# ControllerV2_1_2.net
KiCad netlist of a schematic drawn in Altium Designer
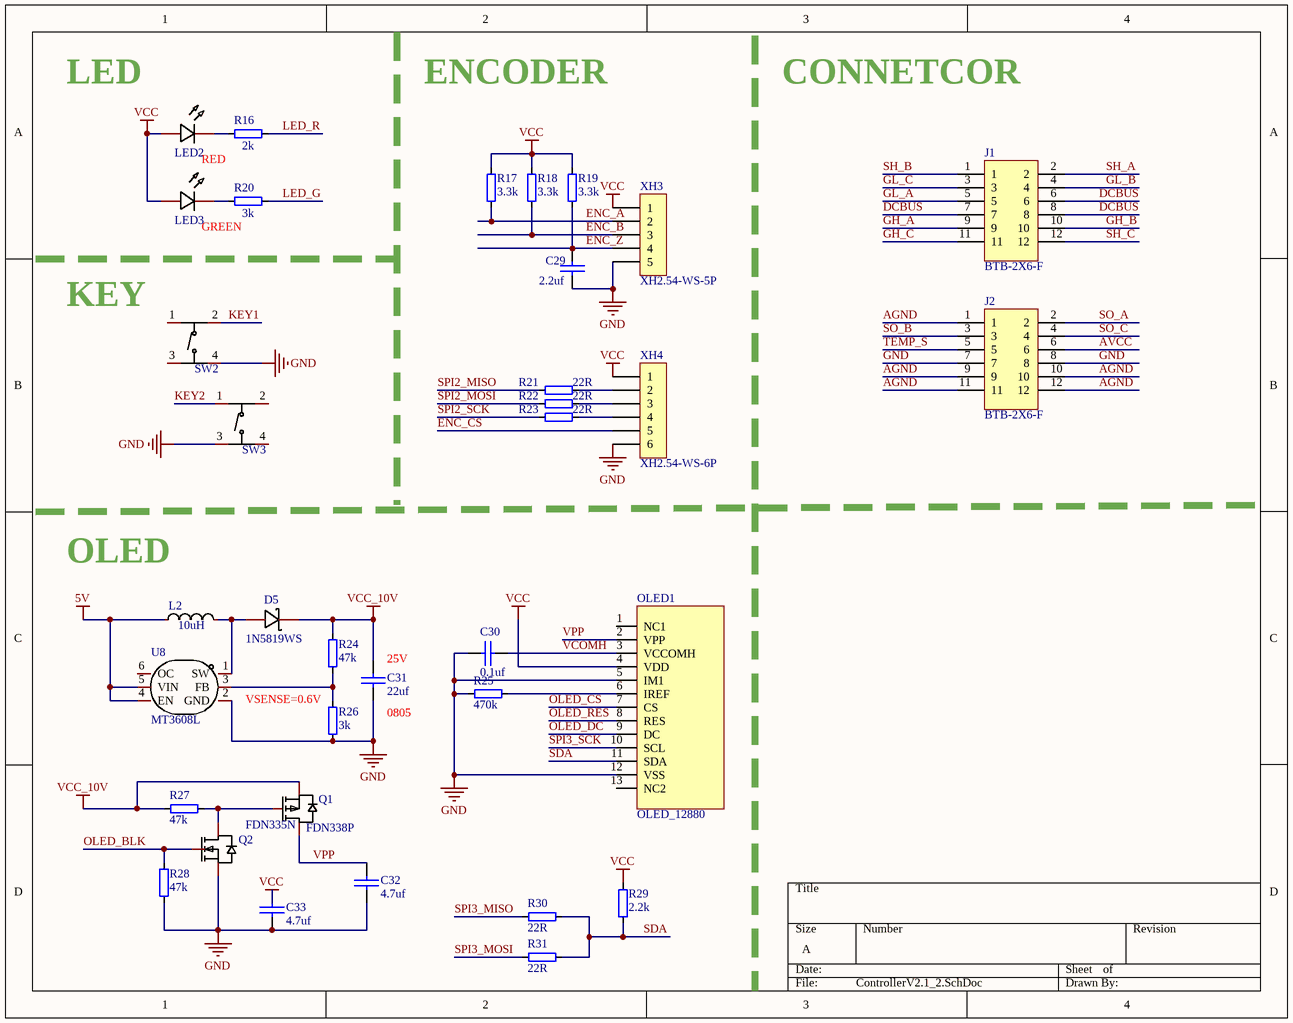
[diagram p0: ControllerV2.1_2.SchDoc]

(export (version "E")
  (design (tool "Eeschema 10.0.6"))
  (components
    (comp (ref "C29")
      (value "2.2uf")
      (footprint "0603C")
      (description "贴片电容")
      (libsource (lib "Controller") (part "CAP"))
    )
    (comp (ref "C30")
      (value "0.1uf")
      (footprint "0603C")
      (description "贴片电容")
      (libsource (lib "Controller") (part "CAP"))
    )
    (comp (ref "C31")
      (value "22uf")
      (footprint "0805C")
      (description "贴片电容")
      (libsource (lib "Controller") (part "CAP"))
    )
    (comp (ref "C32")
      (value "4.7uf")
      (footprint "0603C")
      (description "贴片电容")
      (libsource (lib "Controller") (part "CAP"))
    )
    (comp (ref "C33")
      (value "4.7uf")
      (footprint "0603C")
      (description "贴片电容")
      (libsource (lib "Controller") (part "CAP"))
    )
    (comp (ref "D5")
      (value "1N5819WS")
      (footprint "SOD-323")
      (description "肖特基二极管")
      (fields (field (name "MANUFACTURER") "Hottech(合科泰)"))
      (libsource (lib "Controller") (part "1N5819WS"))
    )
    (comp (ref "J1")
      (value "BTB-2X6-F")
      (footprint "BTB-F-0.8mm-2x6P")
      (description "0.8间距2x6P母座")
      (libsource (lib "Controller") (part "BTB-2X6-F"))
    )
    (comp (ref "J2")
      (value "BTB-2X6-F")
      (footprint "BTB-F-0.8mm-2x6P")
      (description "0.8间距2x6P母座")
      (libsource (lib "Controller") (part "BTB-2X6-F"))
    )
    (comp (ref "L2")
      (value "10uH")
      (footprint "IND-SMD_L3.0-W3.0_SWPA3010S")
      (description "电感值:10uH;精度:±20%;额定电流:920mA;")
      (fields (field (name "MANUFACTURER") "SXN(顺翔诺)") (field (name "MANUFACTURER PART") "SMDRI74-220M"))
      (libsource (lib "Controller") (part "SWPA3015S100MT"))
    )
    (comp (ref "LED2")
      (value "LED_0603-B")
      (footprint "LED_0603")
      (libsource (lib "Controller") (part "LED"))
    )
    (comp (ref "LED3")
      (value "LED_0603-B")
      (footprint "LED_0603")
      (libsource (lib "Controller") (part "LED"))
    )
    (comp (ref "OLED1")
      (value "OLED_12880")
      (footprint "OLED_12880")
      (description "OLED_128*80")
      (libsource (lib "Controller") (part "OLED_12880"))
    )
    (comp (ref "Q1")
      (value "FDN338P")
      (footprint "SOT-23-3")
      (description "P沟道 耐压:20V 电流:2A")
      (fields (field (name "MANUFACTURER") "TECH PUBLIC(台舟)"))
      (libsource (lib "Controller") (part "FDN338P"))
    )
    (comp (ref "Q2")
      (value "FDN335N")
      (footprint "SOT-23-3")
      (description "N沟道 耐压:20V 电流:1.7A")
      (fields (field (name "MANUFACTURER") "TECH PUBLIC(台舟)"))
      (libsource (lib "Controller") (part "FDN335N"))
    )
    (comp (ref "R16")
      (value "2k")
      (footprint "0603R")
      (description "贴片电阻")
      (libsource (lib "Controller") (part "RES"))
    )
    (comp (ref "R17")
      (value "3.3k")
      (footprint "0603R")
      (description "贴片电阻")
      (libsource (lib "Controller") (part "RES"))
    )
    (comp (ref "R18")
      (value "3.3k")
      (footprint "0603R")
      (description "贴片电阻")
      (libsource (lib "Controller") (part "RES"))
    )
    (comp (ref "R19")
      (value "3.3k")
      (footprint "0603R")
      (description "贴片电阻")
      (libsource (lib "Controller") (part "RES"))
    )
    (comp (ref "R20")
      (value "3k")
      (footprint "0603R")
      (description "贴片电阻")
      (libsource (lib "Controller") (part "RES"))
    )
    (comp (ref "R21")
      (value "22R")
      (footprint "0603R")
      (description "贴片电阻")
      (libsource (lib "Controller") (part "RES"))
    )
    (comp (ref "R22")
      (value "22R")
      (footprint "0603R")
      (description "贴片电阻")
      (libsource (lib "Controller") (part "RES"))
    )
    (comp (ref "R23")
      (value "22R")
      (footprint "0603R")
      (description "贴片电阻")
      (libsource (lib "Controller") (part "RES"))
    )
    (comp (ref "R24")
      (value "47k")
      (footprint "0603R")
      (description "贴片电阻")
      (libsource (lib "Controller") (part "RES"))
    )
    (comp (ref "R25")
      (value "470k")
      (footprint "0603R")
      (description "贴片电阻")
      (libsource (lib "Controller") (part "RES"))
    )
    (comp (ref "R26")
      (value "3k")
      (footprint "0603R")
      (description "贴片电阻")
      (libsource (lib "Controller") (part "RES"))
    )
    (comp (ref "R27")
      (value "47k")
      (footprint "0603R")
      (description "贴片电阻")
      (libsource (lib "Controller") (part "RES"))
    )
    (comp (ref "R28")
      (value "47k")
      (footprint "0603R")
      (description "贴片电阻")
      (libsource (lib "Controller") (part "RES"))
    )
    (comp (ref "R29")
      (value "2.2k")
      (footprint "0603R")
      (description "贴片电阻")
      (libsource (lib "Controller") (part "RES"))
    )
    (comp (ref "R30")
      (value "22R")
      (footprint "0603R")
      (description "贴片电阻")
      (libsource (lib "Controller") (part "RES"))
    )
    (comp (ref "R31")
      (value "22R")
      (footprint "0603R")
      (description "贴片电阻")
      (libsource (lib "Controller") (part "RES"))
    )
    (comp (ref "SW2")
      (value "TS-1187A-B-A-B")
      (footprint "TSW SMD-4*4*1.5")
      (description "轻触开关")
      (fields (field (name "MANUFACTURER") "XKB Connectivity(中国星坤)"))
      (libsource (lib "Controller") (part "TS-1187A-B-A-B"))
    )
    (comp (ref "SW3")
      (value "TS-1187A-B-A-B")
      (footprint "TSW SMD-4*4*1.5")
      (description "轻触开关")
      (fields (field (name "MANUFACTURER") "XKB Connectivity(中国星坤)"))
      (libsource (lib "Controller") (part "TS-1187A-B-A-B"))
    )
    (comp (ref "U8")
      (value "MT3608L")
      (footprint "SOT-23-6")
      (fields (field (name "MANUFACTURER") "西安航天民芯"))
      (libsource (lib "Controller") (part "MT3608L"))
    )
    (comp (ref "XH3")
      (value "XH2.54-WS-5P")
      (footprint "XH2.54-WS-5P")
      (libsource (lib "Controller") (part "XH2.54-WS-5P"))
    )
    (comp (ref "XH4")
      (value "XH2.54-WS-6P")
      (footprint "XH2.54-WS-6P")
      (libsource (lib "Controller") (part "XH2.54-WS-6P"))
    )
  )
  (nets
    (net (code "1") (name "/AGND") (class "Default")
      (node (ref "J2") (pin "1") (pinfunction "1_1") (pintype "passive"))
      (node (ref "J2") (pin "10") (pinfunction "10_10") (pintype "passive"))
      (node (ref "J2") (pin "11") (pinfunction "11_11") (pintype "passive"))
      (node (ref "J2") (pin "12") (pinfunction "12_12") (pintype "passive"))
      (node (ref "J2") (pin "9") (pinfunction "9_9") (pintype "passive"))
    )
    (net (code "2") (name "/AVCC") (class "Default")
      (node (ref "J2") (pin "6") (pinfunction "6_6") (pintype "passive"))
    )
    (net (code "3") (name "/DCBUS") (class "Default")
      (node (ref "J1") (pin "6") (pinfunction "6_6") (pintype "passive"))
      (node (ref "J1") (pin "7") (pinfunction "7_7") (pintype "passive"))
      (node (ref "J1") (pin "8") (pinfunction "8_8") (pintype "passive"))
    )
    (net (code "4") (name "/ENC_A") (class "Default")
      (node (ref "R17") (pin "1") (pinfunction "1_1") (pintype "passive"))
      (node (ref "XH3") (pin "2") (pinfunction "2_2") (pintype "passive"))
    )
    (net (code "5") (name "/ENC_B") (class "Default")
      (node (ref "R18") (pin "1") (pinfunction "1_1") (pintype "passive"))
      (node (ref "XH3") (pin "3") (pinfunction "3_3") (pintype "passive"))
    )
    (net (code "6") (name "/ENC_CS") (class "Default")
      (node (ref "XH4") (pin "5") (pinfunction "5_5") (pintype "passive"))
    )
    (net (code "7") (name "/ENC_Z") (class "Default")
      (node (ref "C29") (pin "1") (pinfunction "1_1") (pintype "passive"))
      (node (ref "R19") (pin "1") (pinfunction "1_1") (pintype "passive"))
      (node (ref "XH3") (pin "4") (pinfunction "4_4") (pintype "passive"))
    )
    (net (code "8") (name "/GH_A") (class "Default")
      (node (ref "J1") (pin "9") (pinfunction "9_9") (pintype "passive"))
    )
    (net (code "9") (name "/GH_B") (class "Default")
      (node (ref "J1") (pin "10") (pinfunction "10_10") (pintype "passive"))
    )
    (net (code "10") (name "/GH_C") (class "Default")
      (node (ref "J1") (pin "11") (pinfunction "11_11") (pintype "passive"))
    )
    (net (code "11") (name "/GL_A") (class "Default")
      (node (ref "J1") (pin "5") (pinfunction "5_5") (pintype "passive"))
    )
    (net (code "12") (name "/GL_B") (class "Default")
      (node (ref "J1") (pin "4") (pinfunction "4_4") (pintype "passive"))
    )
    (net (code "13") (name "/GL_C") (class "Default")
      (node (ref "J1") (pin "3") (pinfunction "3_3") (pintype "passive"))
    )
    (net (code "14") (name "/KEY1") (class "Default")
      (node (ref "SW2") (pin "2") (pinfunction "B_2") (pintype "passive"))
    )
    (net (code "15") (name "/KEY2") (class "Default")
      (node (ref "SW3") (pin "1") (pinfunction "A_1") (pintype "passive"))
    )
    (net (code "16") (name "/LED_G") (class "Default")
      (node (ref "R20") (pin "2") (pinfunction "2_2") (pintype "passive"))
    )
    (net (code "17") (name "/LED_R") (class "Default")
      (node (ref "R16") (pin "2") (pinfunction "2_2") (pintype "passive"))
    )
    (net (code "18") (name "/OLED_BLK") (class "Default")
      (node (ref "Q2") (pin "1") (pinfunction "G_1") (pintype "passive"))
      (node (ref "R28") (pin "2") (pinfunction "2_2") (pintype "passive"))
    )
    (net (code "19") (name "/OLED_CS") (class "Default")
      (node (ref "OLED1") (pin "7") (pinfunction "CS_7") (pintype "passive"))
    )
    (net (code "20") (name "/OLED_DC") (class "Default")
      (node (ref "OLED1") (pin "9") (pinfunction "DC_9") (pintype "passive"))
    )
    (net (code "21") (name "/OLED_RES") (class "Default")
      (node (ref "OLED1") (pin "8") (pinfunction "RES_8") (pintype "passive"))
    )
    (net (code "22") (name "/SDA") (class "Default")
      (node (ref "OLED1") (pin "11") (pinfunction "SDA_11") (pintype "passive"))
      (node (ref "R29") (pin "1") (pinfunction "1_1") (pintype "passive"))
      (node (ref "R30") (pin "2") (pinfunction "2_2") (pintype "passive"))
      (node (ref "R31") (pin "2") (pinfunction "2_2") (pintype "passive"))
    )
    (net (code "23") (name "/SH_A") (class "Default")
      (node (ref "J1") (pin "2") (pinfunction "2_2") (pintype "passive"))
    )
    (net (code "24") (name "/SH_B") (class "Default")
      (node (ref "J1") (pin "1") (pinfunction "1_1") (pintype "passive"))
    )
    (net (code "25") (name "/SH_C") (class "Default")
      (node (ref "J1") (pin "12") (pinfunction "12_12") (pintype "passive"))
    )
    (net (code "26") (name "/SO_A") (class "Default")
      (node (ref "J2") (pin "2") (pinfunction "2_2") (pintype "passive"))
    )
    (net (code "27") (name "/SO_B") (class "Default")
      (node (ref "J2") (pin "3") (pinfunction "3_3") (pintype "passive"))
    )
    (net (code "28") (name "/SO_C") (class "Default")
      (node (ref "J2") (pin "4") (pinfunction "4_4") (pintype "passive"))
    )
    (net (code "29") (name "/SPI2_MISO") (class "Default")
      (node (ref "R21") (pin "1") (pinfunction "1_1") (pintype "passive"))
    )
    (net (code "30") (name "/SPI2_MOSI") (class "Default")
      (node (ref "R22") (pin "1") (pinfunction "1_1") (pintype "passive"))
    )
    (net (code "31") (name "/SPI2_SCK") (class "Default")
      (node (ref "R23") (pin "1") (pinfunction "1_1") (pintype "passive"))
    )
    (net (code "32") (name "/SPI3_MISO") (class "Default")
      (node (ref "R30") (pin "1") (pinfunction "1_1") (pintype "passive"))
    )
    (net (code "33") (name "/SPI3_MOSI") (class "Default")
      (node (ref "R31") (pin "1") (pinfunction "1_1") (pintype "passive"))
    )
    (net (code "34") (name "/SPI3_SCK") (class "Default")
      (node (ref "OLED1") (pin "10") (pinfunction "SCL_10") (pintype "passive"))
    )
    (net (code "35") (name "/TEMP_S") (class "Default")
      (node (ref "J2") (pin "5") (pinfunction "5_5") (pintype "passive"))
    )
    (net (code "36") (name "/VCOMH") (class "Default")
      (node (ref "C30") (pin "2") (pinfunction "2_2") (pintype "passive"))
      (node (ref "OLED1") (pin "3") (pinfunction "VCCOMH_3") (pintype "passive"))
    )
    (net (code "37") (name "/VPP") (class "Default")
      (node (ref "C32") (pin "1") (pinfunction "1_1") (pintype "passive"))
      (node (ref "OLED1") (pin "2") (pinfunction "VPP_2") (pintype "passive"))
      (node (ref "Q1") (pin "3") (pinfunction "D_3") (pintype "passive"))
    )
    (net (code "38") (name "5V") (class "Default")
      (node (ref "L2") (pin "1") (pinfunction "1_1") (pintype "passive"))
      (node (ref "U8") (pin "4") (pinfunction "EN_4") (pintype "passive"))
      (node (ref "U8") (pin "5") (pinfunction "VIN_5") (pintype "passive"))
    )
    (net (code "39") (name "GND") (class "Default")
      (node (ref "C29") (pin "2") (pinfunction "2_2") (pintype "passive"))
      (node (ref "C30") (pin "1") (pinfunction "1_1") (pintype "passive"))
      (node (ref "C31") (pin "2") (pinfunction "2_2") (pintype "passive"))
      (node (ref "C32") (pin "2") (pinfunction "2_2") (pintype "passive"))
      (node (ref "C33") (pin "2") (pinfunction "2_2") (pintype "passive"))
      (node (ref "J2") (pin "7") (pinfunction "7_7") (pintype "passive"))
      (node (ref "J2") (pin "8") (pinfunction "8_8") (pintype "passive"))
      (node (ref "OLED1") (pin "12") (pinfunction "VSS_12") (pintype "passive"))
      (node (ref "OLED1") (pin "5") (pinfunction "IM1_5") (pintype "passive"))
      (node (ref "Q2") (pin "2") (pinfunction "S_2") (pintype "passive"))
      (node (ref "R25") (pin "1") (pinfunction "1_1") (pintype "passive"))
      (node (ref "R26") (pin "1") (pinfunction "1_1") (pintype "passive"))
      (node (ref "R28") (pin "1") (pinfunction "1_1") (pintype "passive"))
      (node (ref "SW2") (pin "4") (pinfunction "D_4") (pintype "passive"))
      (node (ref "SW3") (pin "3") (pinfunction "C_3") (pintype "passive"))
      (node (ref "U8") (pin "2") (pinfunction "GND_2") (pintype "passive"))
      (node (ref "XH3") (pin "5") (pinfunction "5_5") (pintype "passive"))
      (node (ref "XH4") (pin "6") (pinfunction "6_6") (pintype "passive"))
    )
    (net (code "40") (name "Net-(D5-A)") (class "Default")
      (node (ref "D5") (pin "2") (pinfunction "A_2") (pintype "passive"))
      (node (ref "L2") (pin "2") (pinfunction "2_2") (pintype "passive"))
      (node (ref "U8") (pin "1") (pinfunction "SW_1") (pintype "passive"))
    )
    (net (code "41") (name "Net-(LED2-C)") (class "Default")
      (node (ref "LED2") (pin "1") (pinfunction "C_1") (pintype "passive"))
      (node (ref "R16") (pin "1") (pinfunction "1_1") (pintype "passive"))
    )
    (net (code "42") (name "Net-(LED3-C)") (class "Default")
      (node (ref "LED3") (pin "1") (pinfunction "C_1") (pintype "passive"))
      (node (ref "R20") (pin "1") (pinfunction "1_1") (pintype "passive"))
    )
    (net (code "43") (name "Net-(OLED1-IREF)") (class "Default")
      (node (ref "OLED1") (pin "6") (pinfunction "IREF_6") (pintype "passive"))
      (node (ref "R25") (pin "2") (pinfunction "2_2") (pintype "passive"))
    )
    (net (code "44") (name "Net-(Q1-G)") (class "Default")
      (node (ref "Q1") (pin "1") (pinfunction "G_1") (pintype "passive"))
      (node (ref "Q2") (pin "3") (pinfunction "D_3") (pintype "passive"))
      (node (ref "R27") (pin "2") (pinfunction "2_2") (pintype "passive"))
    )
    (net (code "45") (name "Net-(R21-Pad2)") (class "Default")
      (node (ref "R21") (pin "2") (pinfunction "2_2") (pintype "passive"))
      (node (ref "XH4") (pin "2") (pinfunction "2_2") (pintype "passive"))
    )
    (net (code "46") (name "Net-(R22-Pad2)") (class "Default")
      (node (ref "R22") (pin "2") (pinfunction "2_2") (pintype "passive"))
      (node (ref "XH4") (pin "3") (pinfunction "3_3") (pintype "passive"))
    )
    (net (code "47") (name "Net-(R23-Pad2)") (class "Default")
      (node (ref "R23") (pin "2") (pinfunction "2_2") (pintype "passive"))
      (node (ref "XH4") (pin "4") (pinfunction "4_4") (pintype "passive"))
    )
    (net (code "48") (name "Net-(U8-FB)") (class "Default")
      (node (ref "R24") (pin "1") (pinfunction "1_1") (pintype "passive"))
      (node (ref "R26") (pin "2") (pinfunction "2_2") (pintype "passive"))
      (node (ref "U8") (pin "3") (pinfunction "FB_3") (pintype "passive"))
    )
    (net (code "49") (name "VCC") (class "Default")
      (node (ref "C33") (pin "1") (pinfunction "1_1") (pintype "passive"))
      (node (ref "LED2") (pin "2") (pinfunction "A_2") (pintype "passive"))
      (node (ref "LED3") (pin "2") (pinfunction "A_2") (pintype "passive"))
      (node (ref "OLED1") (pin "4") (pinfunction "VDD_4") (pintype "passive"))
      (node (ref "R17") (pin "2") (pinfunction "2_2") (pintype "passive"))
      (node (ref "R18") (pin "2") (pinfunction "2_2") (pintype "passive"))
      (node (ref "R19") (pin "2") (pinfunction "2_2") (pintype "passive"))
      (node (ref "R29") (pin "2") (pinfunction "2_2") (pintype "passive"))
      (node (ref "XH3") (pin "1") (pinfunction "1_1") (pintype "passive"))
      (node (ref "XH4") (pin "1") (pinfunction "1_1") (pintype "passive"))
    )
    (net (code "50") (name "VCC_10V") (class "Default")
      (node (ref "C31") (pin "1") (pinfunction "1_1") (pintype "passive"))
      (node (ref "D5") (pin "1") (pinfunction "K_1") (pintype "passive"))
      (node (ref "Q1") (pin "2") (pinfunction "S_2") (pintype "passive"))
      (node (ref "R24") (pin "2") (pinfunction "2_2") (pintype "passive"))
      (node (ref "R27") (pin "1") (pinfunction "1_1") (pintype "passive"))
    )
    (net (code "51") (name "unconnected-(OLED1-NC1-Pad1)") (class "Default")
      (node (ref "OLED1") (pin "1") (pinfunction "NC1_1") (pintype "passive"))
    )
    (net (code "52") (name "unconnected-(OLED1-NC2-Pad13)") (class "Default")
      (node (ref "OLED1") (pin "13") (pinfunction "NC2_13") (pintype "passive"))
    )
    (net (code "53") (name "unconnected-(SW2-A-Pad1)") (class "Default")
      (node (ref "SW2") (pin "1") (pinfunction "A_1") (pintype "passive"))
    )
    (net (code "54") (name "unconnected-(SW2-C-Pad3)") (class "Default")
      (node (ref "SW2") (pin "3") (pinfunction "C_3") (pintype "passive"))
    )
    (net (code "55") (name "unconnected-(SW3-B-Pad2)") (class "Default")
      (node (ref "SW3") (pin "2") (pinfunction "B_2") (pintype "passive"))
    )
    (net (code "56") (name "unconnected-(SW3-D-Pad4)") (class "Default")
      (node (ref "SW3") (pin "4") (pinfunction "D_4") (pintype "passive"))
    )
    (net (code "57") (name "unconnected-(U8-OC-Pad6)") (class "Default")
      (node (ref "U8") (pin "6") (pinfunction "OC_6") (pintype "passive"))
    )
  )
)
